# lights-driver.net
KiCad netlist of a schematic drawn in EAGLE
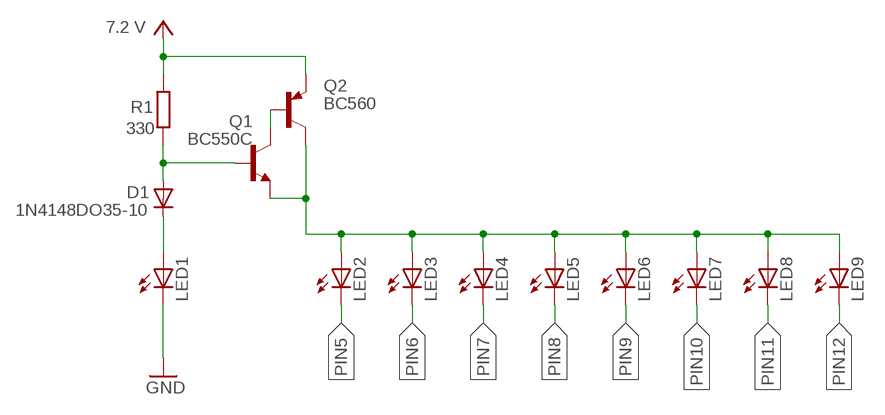
[diagram p0: schematic, sheet 1]

(export (version "E")
  (design (tool "Eeschema 10.0.6"))
  (components
    (comp (ref "D1")
      (value "1N4148DO35-10")
      (footprint "eagle-import:DO35-10")
      (libsource (lib "eagle-import") (part "1N4148DO35-10"))
    )
    (comp (ref "LED1")
      (value "LED3MM")
      (footprint "eagle-import:LED3MM")
      (libsource (lib "eagle-import") (part "LED3MM"))
    )
    (comp (ref "LED2")
      (value "LED3MM")
      (footprint "eagle-import:LED3MM")
      (libsource (lib "eagle-import") (part "LED3MM"))
    )
    (comp (ref "LED3")
      (value "LED3MM")
      (footprint "eagle-import:LED3MM")
      (libsource (lib "eagle-import") (part "LED3MM"))
    )
    (comp (ref "LED4")
      (value "LED3MM")
      (footprint "eagle-import:LED3MM")
      (libsource (lib "eagle-import") (part "LED3MM"))
    )
    (comp (ref "LED5")
      (value "LED3MM")
      (footprint "eagle-import:LED3MM")
      (libsource (lib "eagle-import") (part "LED3MM"))
    )
    (comp (ref "LED6")
      (value "LED3MM")
      (footprint "eagle-import:LED3MM")
      (libsource (lib "eagle-import") (part "LED3MM"))
    )
    (comp (ref "LED7")
      (value "LED3MM")
      (footprint "eagle-import:LED3MM")
      (libsource (lib "eagle-import") (part "LED3MM"))
    )
    (comp (ref "LED8")
      (value "LED3MM")
      (footprint "eagle-import:LED3MM")
      (libsource (lib "eagle-import") (part "LED3MM"))
    )
    (comp (ref "LED9")
      (value "LED3MM")
      (footprint "eagle-import:LED3MM")
      (libsource (lib "eagle-import") (part "LED3MM"))
    )
    (comp (ref "Q1")
      (value "BC550C")
      (footprint "eagle-import:TO92-EBC")
      (libsource (lib "eagle-import") (part "BC550C"))
    )
    (comp (ref "Q2")
      (value "BC560")
      (footprint "eagle-import:TO92-EBC")
      (libsource (lib "eagle-import") (part "BC560"))
    )
    (comp (ref "R1")
      (value "330")
      (footprint "eagle-import:0207_10")
      (libsource (lib "eagle-import") (part "R0207/10"))
    )
  )
  (nets
    (net (code "1") (name "7.2 V") (class "Default")
      (node (ref "Q2") (pin "E") (pinfunction "E_E") (pintype "passive"))
      (node (ref "R1") (pin "2") (pinfunction "2_2") (pintype "passive"))
    )
    (net (code "2") (name "GND") (class "Default")
      (node (ref "LED1") (pin "K") (pinfunction "C_K") (pintype "passive"))
    )
    (net (code "3") (name "Net-(D1-PadA)") (class "Default")
      (node (ref "D1") (pin "A") (pinfunction "A_A") (pintype "passive"))
      (node (ref "Q1") (pin "B") (pinfunction "B_B") (pintype "passive"))
      (node (ref "R1") (pin "1") (pinfunction "1_1") (pintype "passive"))
    )
    (net (code "4") (name "Net-(D1-PadC)") (class "Default")
      (node (ref "D1") (pin "C") (pinfunction "C_C") (pintype "passive"))
      (node (ref "LED1") (pin "A") (pinfunction "A_A") (pintype "passive"))
    )
    (net (code "5") (name "Net-(LED2-PadA)") (class "Default")
      (node (ref "LED2") (pin "A") (pinfunction "A_A") (pintype "passive"))
      (node (ref "LED3") (pin "A") (pinfunction "A_A") (pintype "passive"))
      (node (ref "LED4") (pin "A") (pinfunction "A_A") (pintype "passive"))
      (node (ref "LED5") (pin "A") (pinfunction "A_A") (pintype "passive"))
      (node (ref "LED6") (pin "A") (pinfunction "A_A") (pintype "passive"))
      (node (ref "LED7") (pin "A") (pinfunction "A_A") (pintype "passive"))
      (node (ref "LED8") (pin "A") (pinfunction "A_A") (pintype "passive"))
      (node (ref "LED9") (pin "A") (pinfunction "A_A") (pintype "passive"))
      (node (ref "Q1") (pin "E") (pinfunction "E_E") (pintype "passive"))
      (node (ref "Q2") (pin "C") (pinfunction "C_C") (pintype "passive"))
    )
    (net (code "6") (name "Net-(Q1-PadC)") (class "Default")
      (node (ref "Q1") (pin "C") (pinfunction "C_C") (pintype "passive"))
      (node (ref "Q2") (pin "B") (pinfunction "B_B") (pintype "passive"))
    )
    (net (code "7") (name "PIN5") (class "Default")
      (node (ref "LED2") (pin "K") (pinfunction "C_K") (pintype "passive"))
    )
    (net (code "8") (name "PIN6") (class "Default")
      (node (ref "LED3") (pin "K") (pinfunction "C_K") (pintype "passive"))
    )
    (net (code "9") (name "PIN7") (class "Default")
      (node (ref "LED4") (pin "K") (pinfunction "C_K") (pintype "passive"))
    )
    (net (code "10") (name "PIN8") (class "Default")
      (node (ref "LED5") (pin "K") (pinfunction "C_K") (pintype "passive"))
    )
    (net (code "11") (name "PIN9") (class "Default")
      (node (ref "LED6") (pin "K") (pinfunction "C_K") (pintype "passive"))
    )
    (net (code "12") (name "PIN10") (class "Default")
      (node (ref "LED7") (pin "K") (pinfunction "C_K") (pintype "passive"))
    )
    (net (code "13") (name "PIN11") (class "Default")
      (node (ref "LED8") (pin "K") (pinfunction "C_K") (pintype "passive"))
    )
    (net (code "14") (name "PIN12") (class "Default")
      (node (ref "LED9") (pin "K") (pinfunction "C_K") (pintype "passive"))
    )
  )
)
